# 1_1.net
KiCad netlist of a schematic drawn in Altium Designer
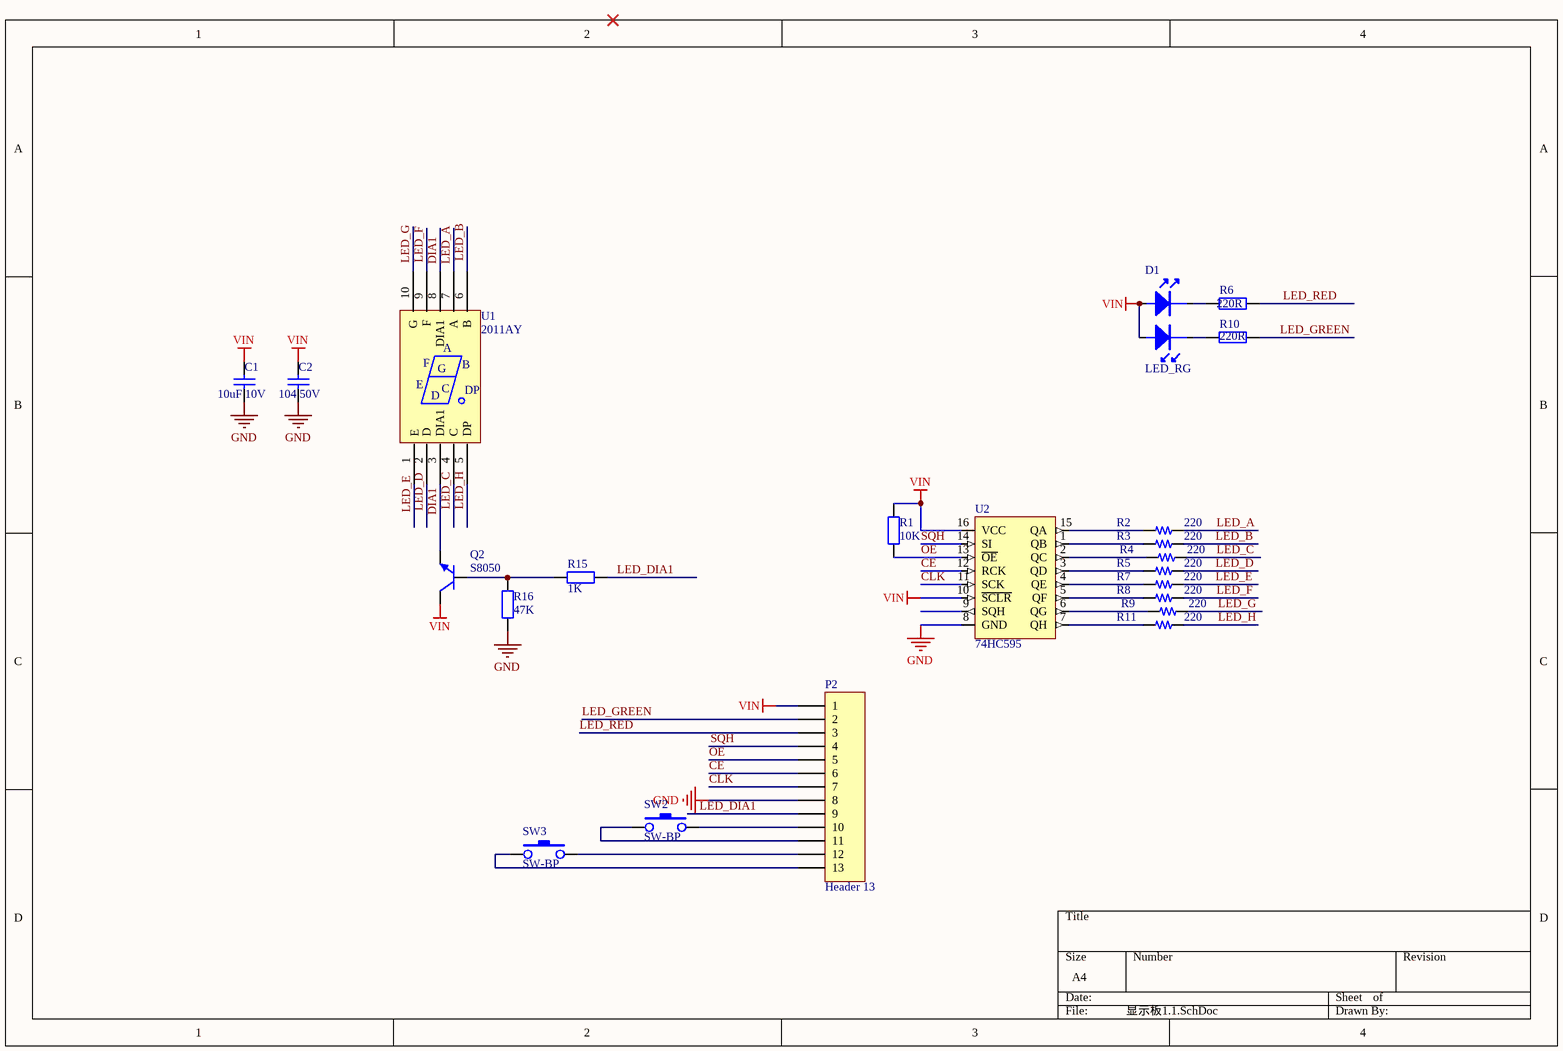
[diagram p0: 显示板1.1.SchDoc]

(export (version "E")
  (design (tool "Eeschema 10.0.6"))
  (components
    (comp (ref "C1")
      (value "10uF 10V")
      (footprint "SMD-0603C")
      (description "贴片电容 10%")
      (libsource (lib "XiaoyI") (part "CAP4"))
    )
    (comp (ref "C2")
      (value "104 50V")
      (footprint "SMD-0603C")
      (description "贴片电容 10%")
      (libsource (lib "XiaoyI") (part "CAP4"))
    )
    (comp (ref "D1") (value "LED_RG") (libsource (lib "电解水杯V1.1_ZM_20210702") (part "LED_RG")))
    (comp (ref "P2")
      (value "Header 13")
      (footprint "13×1.25mmSMT")
      (description "Header, 13-Pin")
      (fields (field (name "PUBLISHER") "Altium Limited"))
      (libsource (lib "Miscellaneous Connectors") (part "Header 13"))
    )
    (comp (ref "Q2")
      (value "S8050")
      (footprint "SOT-23")
      (description "NPN")
      (libsource (lib "XiaoyI") (part "NPN-1"))
    )
    (comp (ref "R1")
      (value "10K")
      (footprint "SMD-0603")
      (description "贴片电阻 5%")
      (libsource (lib "") (part "RES0_1"))
    )
    (comp (ref "R2") (value "220") (footprint "0603R") (description "R") (libsource (lib "JRJ_1") (part "R")))
    (comp (ref "R3") (value "220") (footprint "0603R") (description "R") (libsource (lib "JRJ_1") (part "R")))
    (comp (ref "R4") (value "220") (footprint "0603R") (description "R") (libsource (lib "JRJ_1") (part "R")))
    (comp (ref "R5") (value "220") (footprint "0603R") (description "R") (libsource (lib "JRJ_1") (part "R")))
    (comp (ref "R6")
      (value "220R")
      (footprint "SMD-0603")
      (description "贴片电阻 5%")
      (libsource (lib "") (part "RES0_2"))
    )
    (comp (ref "R7") (value "220") (footprint "0603R") (description "R") (libsource (lib "JRJ_1") (part "R")))
    (comp (ref "R8") (value "220") (footprint "0603R") (description "R") (libsource (lib "JRJ_1") (part "R")))
    (comp (ref "R9") (value "220") (footprint "0603R") (description "R") (libsource (lib "JRJ_1") (part "R")))
    (comp (ref "R10")
      (value "220R")
      (footprint "SMD-0603")
      (description "贴片电阻 5%")
      (libsource (lib "") (part "RES0_2"))
    )
    (comp (ref "R11")
      (value "220")
      (footprint "0603R")
      (description "R")
      (libsource (lib "JRJ_1") (part "R"))
    )
    (comp (ref "R15")
      (value "1K")
      (footprint "SMD-0603")
      (description "贴片电阻 5%")
      (libsource (lib "ABB") (part "RES0"))
    )
    (comp (ref "R16")
      (value "47K")
      (footprint "SMD-0603")
      (description "贴片电阻 5%")
      (libsource (lib "") (part "RES0_3"))
    )
    (comp (ref "SW2")
      (value "SW-BP")
      (footprint "KEY_4X4")
      (description "3*6*3.5侧贴按键(编带)")
      (libsource (lib "XiaoyI") (part "SW-BP"))
    )
    (comp (ref "SW3")
      (value "SW-BP")
      (footprint "KEY_4X4")
      (description "3*6*3.5侧贴按键(编带)")
      (libsource (lib "XiaoyI") (part "SW-BP"))
    )
    (comp (ref "U1")
      (value "2011AY")
      (footprint "2011AY")
      (libsource (lib "电解水杯V1.1_ZM_20210702") (part "2011AY"))
    )
    (comp (ref "U2")
      (value "74HC595")
      (footprint "SSOP-16")
      (description "逻辑IC")
      (libsource (lib "ABB") (part "74HC595"))
    )
  )
  (nets
    (net (code "1") (name "/CE") (class "Default")
      (node (ref "P2") (pin "6") (pinfunction "6_6") (pintype "passive"))
      (node (ref "U2") (pin "12") (pinfunction "RCK_12") (pintype "input"))
    )
    (net (code "2") (name "/CLK") (class "Default")
      (node (ref "P2") (pin "7") (pinfunction "7_7") (pintype "passive"))
      (node (ref "U2") (pin "11") (pinfunction "SCK_11") (pintype "input"))
    )
    (net (code "3") (name "/DIA1") (class "Default")
      (node (ref "Q2") (pin "2") (pinfunction "E_2") (pintype "passive"))
      (node (ref "U1") (pin "3") (pinfunction "DIA1_3") (pintype "passive"))
      (node (ref "U1") (pin "8") (pinfunction "DIA1_8") (pintype "passive"))
    )
    (net (code "4") (name "/LED_A") (class "Default")
      (node (ref "R2") (pin "2") (pintype "passive"))
      (node (ref "U1") (pin "7") (pinfunction "A_7") (pintype "passive"))
    )
    (net (code "5") (name "/LED_B") (class "Default")
      (node (ref "R3") (pin "2") (pintype "passive"))
      (node (ref "U1") (pin "6") (pinfunction "B_6") (pintype "passive"))
    )
    (net (code "6") (name "/LED_C") (class "Default")
      (node (ref "R4") (pin "2") (pintype "passive"))
      (node (ref "U1") (pin "4") (pinfunction "C_4") (pintype "passive"))
    )
    (net (code "7") (name "/LED_D") (class "Default")
      (node (ref "R5") (pin "2") (pintype "passive"))
      (node (ref "U1") (pin "2") (pinfunction "D_2") (pintype "passive"))
    )
    (net (code "8") (name "/LED_DIA1") (class "Default")
      (node (ref "P2") (pin "9") (pinfunction "9_9") (pintype "passive"))
      (node (ref "R15") (pin "1") (pinfunction "1_1") (pintype "passive"))
    )
    (net (code "9") (name "/LED_E") (class "Default")
      (node (ref "R7") (pin "2") (pintype "passive"))
      (node (ref "U1") (pin "1") (pinfunction "E_1") (pintype "passive"))
    )
    (net (code "10") (name "/LED_F") (class "Default")
      (node (ref "R8") (pin "2") (pintype "passive"))
      (node (ref "U1") (pin "9") (pinfunction "F_9") (pintype "passive"))
    )
    (net (code "11") (name "/LED_G") (class "Default")
      (node (ref "R9") (pin "2") (pintype "passive"))
      (node (ref "U1") (pin "10") (pinfunction "G_10") (pintype "passive"))
    )
    (net (code "12") (name "/LED_GREEN") (class "Default")
      (node (ref "P2") (pin "2") (pinfunction "2_2") (pintype "passive"))
      (node (ref "R10") (pin "2") (pinfunction "2_2") (pintype "passive"))
    )
    (net (code "13") (name "/LED_H") (class "Default")
      (node (ref "R11") (pin "2") (pintype "passive"))
      (node (ref "U1") (pin "5") (pinfunction "DP_5") (pintype "passive"))
    )
    (net (code "14") (name "/LED_RED") (class "Default")
      (node (ref "P2") (pin "3") (pinfunction "3_3") (pintype "passive"))
      (node (ref "R6") (pin "2") (pinfunction "2_2") (pintype "passive"))
    )
    (net (code "15") (name "/OE") (class "Default")
      (node (ref "P2") (pin "5") (pinfunction "5_5") (pintype "passive"))
      (node (ref "R1") (pin "1") (pinfunction "1_1") (pintype "passive"))
      (node (ref "U2") (pin "13") (pinfunction "~{OE}_13") (pintype "input"))
    )
    (net (code "16") (name "/SQH") (class "Default")
      (node (ref "P2") (pin "4") (pinfunction "4_4") (pintype "passive"))
      (node (ref "U2") (pin "14") (pinfunction "SI_14") (pintype "input"))
    )
    (net (code "17") (name "GND") (class "Default")
      (node (ref "C1") (pin "1") (pinfunction "1_1") (pintype "passive"))
      (node (ref "C2") (pin "1") (pinfunction "1_1") (pintype "passive"))
      (node (ref "P2") (pin "8") (pinfunction "8_8") (pintype "passive"))
      (node (ref "R16") (pin "2") (pinfunction "2_2") (pintype "passive"))
      (node (ref "U2") (pin "8") (pinfunction "GND_8") (pintype "power_in"))
    )
    (net (code "18") (name "Net-(D1-Pad1)") (class "Default")
      (node (ref "D1") (pin "1") (pinfunction "1_1") (pintype "passive"))
      (node (ref "R10") (pin "1") (pinfunction "1_1") (pintype "passive"))
    )
    (net (code "19") (name "Net-(D1-Pad3)") (class "Default")
      (node (ref "D1") (pin "3") (pinfunction "3_3") (pintype "passive"))
      (node (ref "R6") (pin "1") (pinfunction "1_1") (pintype "passive"))
    )
    (net (code "20") (name "Net-(P2-Pad10)") (class "Default")
      (node (ref "P2") (pin "10") (pinfunction "10_10") (pintype "passive"))
      (node (ref "SW2") (pin "2") (pinfunction "2_2") (pintype "passive"))
    )
    (net (code "21") (name "Net-(P2-Pad11)") (class "Default")
      (node (ref "P2") (pin "11") (pinfunction "11_11") (pintype "passive"))
      (node (ref "SW2") (pin "1") (pinfunction "1_1") (pintype "passive"))
    )
    (net (code "22") (name "Net-(P2-Pad12)") (class "Default")
      (node (ref "P2") (pin "12") (pinfunction "12_12") (pintype "passive"))
      (node (ref "SW3") (pin "2") (pinfunction "2_2") (pintype "passive"))
    )
    (net (code "23") (name "Net-(P2-Pad13)") (class "Default")
      (node (ref "P2") (pin "13") (pinfunction "13_13") (pintype "passive"))
      (node (ref "SW3") (pin "1") (pinfunction "1_1") (pintype "passive"))
    )
    (net (code "24") (name "Net-(Q2-B)") (class "Default")
      (node (ref "Q2") (pin "1") (pinfunction "B_1") (pintype "passive"))
      (node (ref "R15") (pin "2") (pinfunction "2_2") (pintype "passive"))
      (node (ref "R16") (pin "1") (pinfunction "1_1") (pintype "passive"))
    )
    (net (code "25") (name "Net-(U2-QA)") (class "Default")
      (node (ref "R2") (pin "1") (pintype "passive"))
      (node (ref "U2") (pin "15") (pinfunction "QA_15") (pintype "output"))
    )
    (net (code "26") (name "Net-(U2-QB)") (class "Default")
      (node (ref "R3") (pin "1") (pintype "passive"))
      (node (ref "U2") (pin "1") (pinfunction "QB_1") (pintype "output"))
    )
    (net (code "27") (name "Net-(U2-QC)") (class "Default")
      (node (ref "R4") (pin "1") (pintype "passive"))
      (node (ref "U2") (pin "2") (pinfunction "QC_2") (pintype "output"))
    )
    (net (code "28") (name "Net-(U2-QD)") (class "Default")
      (node (ref "R5") (pin "1") (pintype "passive"))
      (node (ref "U2") (pin "3") (pinfunction "QD_3") (pintype "output"))
    )
    (net (code "29") (name "Net-(U2-QE)") (class "Default")
      (node (ref "R7") (pin "1") (pintype "passive"))
      (node (ref "U2") (pin "4") (pinfunction "QE_4") (pintype "output"))
    )
    (net (code "30") (name "Net-(U2-QF)") (class "Default")
      (node (ref "R8") (pin "1") (pintype "passive"))
      (node (ref "U2") (pin "5") (pinfunction "QF_5") (pintype "output"))
    )
    (net (code "31") (name "Net-(U2-QG)") (class "Default")
      (node (ref "R9") (pin "1") (pintype "passive"))
      (node (ref "U2") (pin "6") (pinfunction "QG_6") (pintype "output"))
    )
    (net (code "32") (name "Net-(U2-QH)") (class "Default")
      (node (ref "R11") (pin "1") (pintype "passive"))
      (node (ref "U2") (pin "7") (pinfunction "QH_7") (pintype "output"))
    )
    (net (code "33") (name "VIN") (class "Default")
      (node (ref "C1") (pin "2") (pinfunction "2_2") (pintype "passive"))
      (node (ref "C2") (pin "2") (pinfunction "2_2") (pintype "passive"))
      (node (ref "D1") (pin "2") (pinfunction "2_2") (pintype "passive"))
      (node (ref "D1") (pin "4") (pinfunction "4_4") (pintype "passive"))
      (node (ref "P2") (pin "1") (pinfunction "1_1") (pintype "passive"))
      (node (ref "Q2") (pin "3") (pinfunction "C_3") (pintype "passive"))
      (node (ref "R1") (pin "2") (pinfunction "2_2") (pintype "passive"))
      (node (ref "U2") (pin "10") (pinfunction "~{SCLR}_10") (pintype "input"))
      (node (ref "U2") (pin "16") (pinfunction "VCC_16") (pintype "power_in"))
    )
    (net (code "34") (name "unconnected-(U2-SQH-Pad9)") (class "Default")
      (node (ref "U2") (pin "9") (pinfunction "SQH_9") (pintype "output"))
    )
  )
)
